# ORing_Controller_and_FETs.net
KiCad netlist of a schematic drawn in Altium Designer
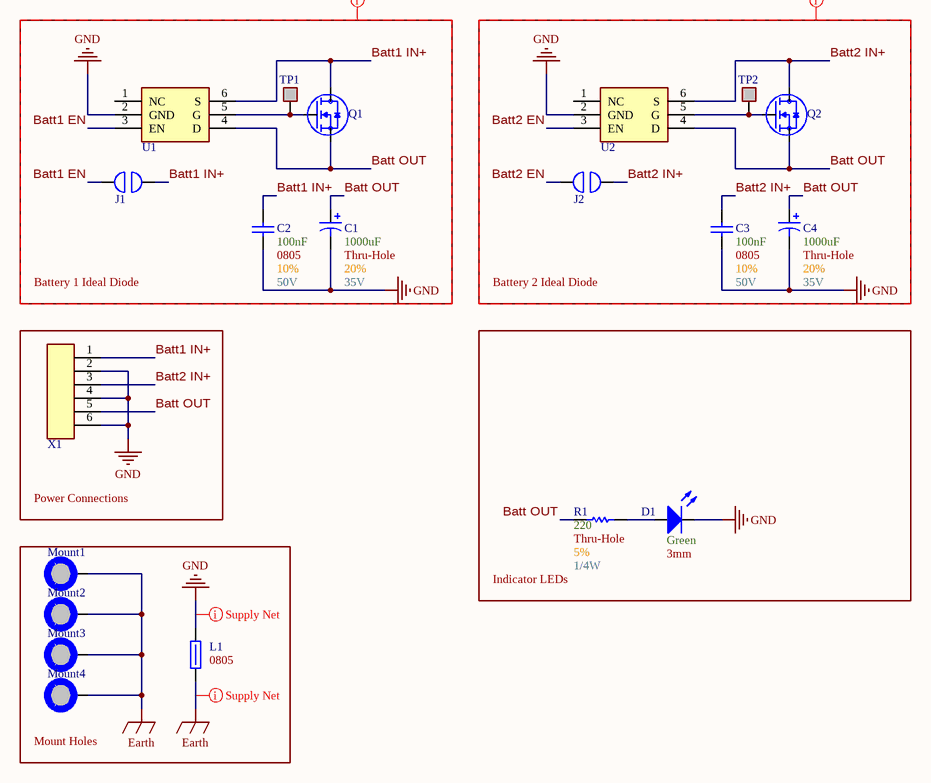
[diagram p0: ORing Controller and FETs.SchDoc]

(export (version "E")
  (design (tool "Eeschema 10.0.6"))
  (components
    (comp (ref "C1")
      (value "[Cap] Thru-Hole 1000uF 20% 35V")
      (footprint "[Cap] Thru-Hole Polarized 10mm")
      (description "35PK1000MEFC10X20")
      (fields
        (field (name "MAX VOLTAGE") "35V")
        (field (name "SIZE PACKAGE") "Thru-Hole")
        (field (name "TOLERANCE") "20%")
        (field (name "CAPACITANCE") "1000uF")
      )
      (libsource (lib "Capacitors") (part "[Cap] Thru-Hole 1000uF 20% 35V"))
    )
    (comp (ref "C2")
      (value "[Cap] 0805 0.1uF 10% 50V")
      (footprint "[Cap] SMD 0805")
      (description "CL21B104KBCNNNC")
      (fields
        (field (name "MAX VOLTAGE") "50V")
        (field (name "SIZE PACKAGE") "0805")
        (field (name "TOLERANCE") "10%")
        (field (name "CAPACITANCE") "100nF")
      )
      (libsource (lib "Capacitors") (part "[Cap] 0805 0.1uF 10% 50V"))
    )
    (comp (ref "C3")
      (value "[Cap] 0805 0.1uF 10% 50V")
      (footprint "[Cap] SMD 0805")
      (description "CL21B104KBCNNNC")
      (fields
        (field (name "MAX VOLTAGE") "50V")
        (field (name "SIZE PACKAGE") "0805")
        (field (name "TOLERANCE") "10%")
        (field (name "CAPACITANCE") "100nF")
      )
      (libsource (lib "Capacitors") (part "[Cap] 0805 0.1uF 10% 50V"))
    )
    (comp (ref "C4")
      (value "[Cap] Thru-Hole 1000uF 20% 35V")
      (footprint "[Cap] Thru-Hole Polarized 10mm")
      (description "35PK1000MEFC10X20")
      (fields
        (field (name "MAX VOLTAGE") "35V")
        (field (name "SIZE PACKAGE") "Thru-Hole")
        (field (name "TOLERANCE") "20%")
        (field (name "CAPACITANCE") "1000uF")
      )
      (libsource (lib "Capacitors") (part "[Cap] Thru-Hole 1000uF 20% 35V"))
    )
    (comp (ref "D1")
      (value "[LED] Thru-Hole 3mm Green")
      (footprint "[LED] Thru-Hole 3mm")
      (description "151031VS06000")
      (fields (field (name "COLOR") "Green") (field (name "LENS DIAMETER") "3mm"))
      (libsource (lib "LEDs") (part "[LED] Thru-Hole 3mm Green"))
    )
    (comp (ref "J1")
      (value "[Jumper] Thru-Hole 2pin")
      (footprint "[Jumper] Thru-Hole 2pin")
      (libsource (lib "Misc Components") (part "[Jumper] Thru-Hole 2pin"))
    )
    (comp (ref "J2")
      (value "[Jumper] Thru-Hole 2pin")
      (footprint "[Jumper] Thru-Hole 2pin")
      (libsource (lib "Misc Components") (part "[Jumper] Thru-Hole 2pin"))
    )
    (comp (ref "L1")
      (value "652-MH2029-300Y")
      (footprint "[Ferrite] SMD 0805")
      (fields (field (name "SIZE PACKAGE") "0805"))
      (libsource (lib "Ferrite Beads") (part "[Ferrite] SMD 0805 3A 30ohm"))
    )
    (comp (ref "Mount1")
      (value "M3 Mount Hole")
      (footprint "[Mount] M3 Mount Hole")
      (description "Place at least 4.5mm from board edge. Plated.")
      (libsource (lib "Misc Components") (part "[Mount] M3 Mount Hole"))
    )
    (comp (ref "Mount2")
      (value "M3 Mount Hole")
      (footprint "[Mount] M3 Mount Hole")
      (description "Place at least 4.5mm from board edge. Plated.")
      (libsource (lib "Misc Components") (part "[Mount] M3 Mount Hole"))
    )
    (comp (ref "Mount3")
      (value "M3 Mount Hole")
      (footprint "[Mount] M3 Mount Hole")
      (description "Place at least 4.5mm from board edge. Plated.")
      (libsource (lib "Misc Components") (part "[Mount] M3 Mount Hole"))
    )
    (comp (ref "Mount4")
      (value "M3 Mount Hole")
      (footprint "[Mount] M3 Mount Hole")
      (description "Place at least 4.5mm from board edge. Plated.")
      (libsource (lib "Misc Components") (part "[Mount] M3 Mount Hole"))
    )
    (comp (ref "Q1")
      (value "NMOS")
      (footprint "[NMOS] SMD 40V 509A")
      (description "NTMFS0D4N04XMT1G")
      (libsource (lib "Transistors") (part "[NMOS] SMD 40V 509A"))
    )
    (comp (ref "Q2")
      (value "NMOS")
      (footprint "[NMOS] SMD 40V 509A")
      (description "NTMFS0D4N04XMT1G")
      (libsource (lib "Transistors") (part "[NMOS] SMD 40V 509A"))
    )
    (comp (ref "R1")
      (value "[220] Thru-Hole 5% 1/4W")
      (footprint "[Res] Thru-Hole 1/4W")
      (description "CFR-25JR-52-220R")
      (fields
        (field (name "SIZE PACKAGE") "Thru-Hole")
        (field (name "WATTAGE") "1/4W")
        (field (name "TOLERANCE") "5%")
        (field (name "RESISTANCE") "220")
      )
      (libsource (lib "Resistors") (part "[220] Thru-Hole 5% 1/4W"))
    )
    (comp (ref "TP1")
      (value "[THM] Thru-Hole")
      (footprint "[THM] White")
      (description "5012")
      (libsource (lib "Test Points") (part "[THM] Thru-Hole"))
    )
    (comp (ref "TP2")
      (value "[THM] Thru-Hole")
      (footprint "[THM] White")
      (description "5012")
      (libsource (lib "Test Points") (part "[THM] Thru-Hole"))
    )
    (comp (ref "U1")
      (value "[ORing] NMOS Controller")
      (footprint "[ORing] NMOS Controller")
      (description "NCV68061SNAIT1G")
      (libsource (lib "ICs") (part "[ORing] NMOS Controller"))
    )
    (comp (ref "U2")
      (value "[ORing] NMOS Controller")
      (footprint "[ORing] NMOS Controller")
      (description "NCV68061SNAIT1G")
      (libsource (lib "ICs") (part "[ORing] NMOS Controller"))
    )
    (comp (ref "X1")
      (value "6pin Screw Terminal")
      (footprint "[Screw Terminal] 6pin 5mm")
      (description "TB002-500-06BE")
      (libsource (lib "Connectors") (part "[Screw Terminal] 6pin"))
    )
  )
  (nets
    (net (code "1") (name "/Batt OUT") (class "Default")
      (node (ref "C1") (pin "1") (pinfunction "1_1") (pintype "passive"))
      (node (ref "C4") (pin "1") (pinfunction "1_1") (pintype "passive"))
      (node (ref "Q1") (pin "1") (pinfunction "Source_1") (pintype "passive"))
      (node (ref "Q2") (pin "1") (pinfunction "Source_1") (pintype "passive"))
      (node (ref "R1") (pin "1") (pinfunction "1_1") (pintype "passive"))
      (node (ref "U1") (pin "4") (pinfunction "D_4") (pintype "passive"))
      (node (ref "U2") (pin "4") (pinfunction "D_4") (pintype "passive"))
      (node (ref "X1") (pin "5") (pintype "power_in"))
    )
    (net (code "2") (name "/Batt1 EN") (class "Default")
      (node (ref "J1") (pin "1") (pintype "passive"))
      (node (ref "U1") (pin "3") (pinfunction "EN_3") (pintype "passive"))
    )
    (net (code "3") (name "/Batt1 IN+") (class "Default")
      (node (ref "C2") (pin "1") (pinfunction "1_1") (pintype "passive"))
      (node (ref "J1") (pin "2") (pintype "passive"))
      (node (ref "Q1") (pin "3") (pinfunction "Drain_3") (pintype "passive"))
      (node (ref "U1") (pin "6") (pinfunction "S_6") (pintype "passive"))
      (node (ref "X1") (pin "1") (pintype "power_in"))
    )
    (net (code "4") (name "/Batt2 EN") (class "Default")
      (node (ref "J2") (pin "1") (pintype "passive"))
      (node (ref "U2") (pin "3") (pinfunction "EN_3") (pintype "passive"))
    )
    (net (code "5") (name "/Batt2 IN+") (class "Default")
      (node (ref "C3") (pin "1") (pinfunction "1_1") (pintype "passive"))
      (node (ref "J2") (pin "2") (pintype "passive"))
      (node (ref "Q2") (pin "3") (pinfunction "Drain_3") (pintype "passive"))
      (node (ref "U2") (pin "6") (pinfunction "S_6") (pintype "passive"))
      (node (ref "X1") (pin "3") (pintype "power_in"))
    )
    (net (code "6") (name "Earth") (class "Default")
      (node (ref "L1") (pin "1") (pinfunction "1_1") (pintype "passive"))
      (node (ref "Mount1") (pin "1") (pintype "power_in"))
      (node (ref "Mount2") (pin "1") (pintype "power_in"))
      (node (ref "Mount3") (pin "1") (pintype "power_in"))
      (node (ref "Mount4") (pin "1") (pintype "power_in"))
    )
    (net (code "7") (name "GND") (class "Default")
      (node (ref "C1") (pin "2") (pinfunction "2_2") (pintype "passive"))
      (node (ref "C2") (pin "2") (pinfunction "2_2") (pintype "passive"))
      (node (ref "C3") (pin "2") (pinfunction "2_2") (pintype "passive"))
      (node (ref "C4") (pin "2") (pinfunction "2_2") (pintype "passive"))
      (node (ref "D1") (pin "2") (pinfunction "Cathode_2") (pintype "passive"))
      (node (ref "L1") (pin "2") (pinfunction "2_2") (pintype "passive"))
      (node (ref "U1") (pin "2") (pinfunction "GND_2") (pintype "passive"))
      (node (ref "U2") (pin "2") (pinfunction "GND_2") (pintype "passive"))
      (node (ref "X1") (pin "2") (pintype "power_in"))
      (node (ref "X1") (pin "4") (pintype "power_in"))
      (node (ref "X1") (pin "6") (pintype "power_in"))
    )
    (net (code "8") (name "Net-(D1-Anode)") (class "Default")
      (node (ref "D1") (pin "1") (pinfunction "Anode_1") (pintype "passive"))
      (node (ref "R1") (pin "2") (pinfunction "2_2") (pintype "passive"))
    )
    (net (code "9") (name "Net-(Q1-Gate)") (class "Default")
      (node (ref "Q1") (pin "2") (pinfunction "Gate_2") (pintype "passive"))
      (node (ref "TP1") (pin "1") (pinfunction "1_1") (pintype "passive"))
      (node (ref "U1") (pin "5") (pinfunction "G_5") (pintype "passive"))
    )
    (net (code "10") (name "Net-(Q2-Gate)") (class "Default")
      (node (ref "Q2") (pin "2") (pinfunction "Gate_2") (pintype "passive"))
      (node (ref "TP2") (pin "1") (pinfunction "1_1") (pintype "passive"))
      (node (ref "U2") (pin "5") (pinfunction "G_5") (pintype "passive"))
    )
    (net (code "11") (name "unconnected-(U1-NC-Pad1)") (class "Default")
      (node (ref "U1") (pin "1") (pinfunction "NC_1") (pintype "passive"))
    )
    (net (code "12") (name "unconnected-(U2-NC-Pad1)") (class "Default")
      (node (ref "U2") (pin "1") (pinfunction "NC_1") (pintype "passive"))
    )
  )
)
